# XL6019.net
KiCad netlist of a schematic drawn in Altium Designer
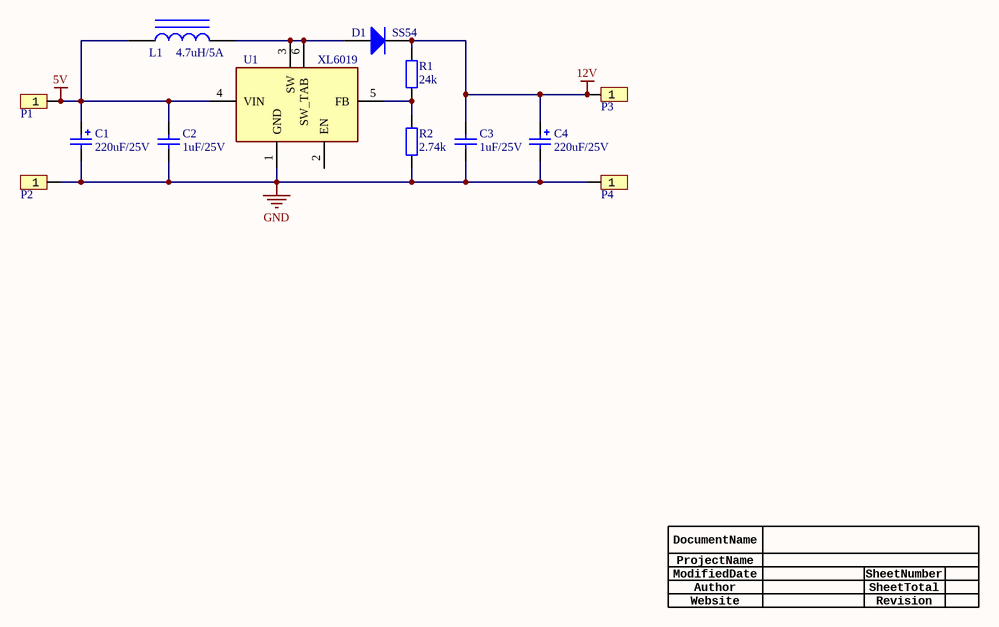
[diagram p0: XL6019.SchDoc]

(export (version "E")
  (design (tool "Eeschema 10.0.6"))
  (components
    (comp (ref "C1")
      (value "220uF/25V")
      (footprint "C_SMD-8X10")
      (description "贴片电容-有极性")
      (libsource (lib "Power_Lib_Altium") (part "CAP-POL"))
    )
    (comp (ref "C2")
      (value "1uF/25V")
      (footprint "CAP-0603")
      (description "贴片电容")
      (libsource (lib "Power_Lib_Altium") (part "CAP"))
    )
    (comp (ref "C3")
      (value "1uF/25V")
      (footprint "CAP-0603")
      (description "贴片电容")
      (libsource (lib "Power_Lib_Altium") (part "CAP"))
    )
    (comp (ref "C4")
      (value "220uF/25V")
      (footprint "C_SMD-8X10")
      (description "贴片电容-有极性")
      (libsource (lib "Power_Lib_Altium") (part "CAP-POL"))
    )
    (comp (ref "D1")
      (value "SS54")
      (footprint "DO-214AA/SMB")
      (description "二极管")
      (libsource (lib "Power_Lib_Altium") (part "DIODE"))
    )
    (comp (ref "L1")
      (value "4.7uH/5A")
      (footprint "L-0630")
      (description "电感")
      (libsource (lib "Power_Lib_Altium") (part "INDUCTOR"))
    )
    (comp (ref "P1")
      (value "HDR1x2_2.54")
      (footprint "HDR1X1_2.54")
      (description "Header")
      (libsource (lib "Power_Lib_Altium") (part "HDR1x1_2.54"))
    )
    (comp (ref "P2")
      (value "HDR1x2_2.54")
      (footprint "HDR1X1_2.54")
      (description "Header")
      (libsource (lib "Power_Lib_Altium") (part "HDR1x1_2.54"))
    )
    (comp (ref "P3")
      (value "HDR1x2_2.54")
      (footprint "HDR1X1_2.54")
      (description "Header")
      (libsource (lib "") (part "HDR1x1_2.54_1"))
    )
    (comp (ref "P4")
      (value "HDR1x2_2.54")
      (footprint "HDR1X1_2.54")
      (description "Header")
      (libsource (lib "") (part "HDR1x1_2.54_1"))
    )
    (comp (ref "R1")
      (value "24k")
      (footprint "R-0603")
      (description "贴片电阻")
      (libsource (lib "Power_Lib_Altium") (part "RES"))
    )
    (comp (ref "R2")
      (value "2.74k")
      (footprint "R-0603")
      (description "贴片电阻")
      (libsource (lib "Power_Lib_Altium") (part "RES"))
    )
    (comp (ref "U1")
      (value "XL6019")
      (footprint "TO-263-5")
      (description "DC-DC")
      (fields (field (name "MANUFACTURER_PART_NUMBER") "FT232RL") (field (name "RS PART NUMBER") "0406580P"))
      (libsource (lib "Power_Lib_Altium") (part "XL6019"))
    )
  )
  (nets
    (net (code "1") (name "5V") (class "Default")
      (node (ref "C1") (pin "1") (pinfunction "1_1") (pintype "passive"))
      (node (ref "C2") (pin "2") (pinfunction "2_2") (pintype "passive"))
      (node (ref "L1") (pin "1") (pinfunction "1_1") (pintype "passive"))
      (node (ref "P1") (pin "1") (pinfunction "1_1") (pintype "passive"))
      (node (ref "U1") (pin "4") (pinfunction "VIN_4") (pintype "power_in"))
    )
    (net (code "2") (name "12V") (class "Default")
      (node (ref "C3") (pin "2") (pinfunction "2_2") (pintype "passive"))
      (node (ref "C4") (pin "1") (pinfunction "1_1") (pintype "passive"))
      (node (ref "D1") (pin "2") (pinfunction "K_2") (pintype "passive"))
      (node (ref "P3") (pin "1") (pinfunction "1_1") (pintype "passive"))
      (node (ref "R1") (pin "2") (pinfunction "2_2") (pintype "passive"))
    )
    (net (code "3") (name "GND") (class "Default")
      (node (ref "C1") (pin "2") (pinfunction "2_2") (pintype "passive"))
      (node (ref "C2") (pin "1") (pinfunction "1_1") (pintype "passive"))
      (node (ref "C3") (pin "1") (pinfunction "1_1") (pintype "passive"))
      (node (ref "C4") (pin "2") (pinfunction "2_2") (pintype "passive"))
      (node (ref "P2") (pin "1") (pinfunction "1_1") (pintype "passive"))
      (node (ref "P4") (pin "1") (pinfunction "1_1") (pintype "passive"))
      (node (ref "R2") (pin "1") (pinfunction "1_1") (pintype "passive"))
      (node (ref "U1") (pin "1") (pinfunction "GND_1") (pintype "passive"))
    )
    (net (code "4") (name "Net-(D1-A)") (class "Default")
      (node (ref "D1") (pin "1") (pinfunction "A_1") (pintype "passive"))
      (node (ref "L1") (pin "2") (pinfunction "2_2") (pintype "passive"))
      (node (ref "U1") (pin "3") (pinfunction "SW_3") (pintype "passive"))
      (node (ref "U1") (pin "6") (pinfunction "SW_TAB_6") (pintype "passive"))
    )
    (net (code "5") (name "Net-(U1-FB)") (class "Default")
      (node (ref "R1") (pin "1") (pinfunction "1_1") (pintype "passive"))
      (node (ref "R2") (pin "2") (pinfunction "2_2") (pintype "passive"))
      (node (ref "U1") (pin "5") (pinfunction "FB_5") (pintype "power_in"))
    )
    (net (code "6") (name "unconnected-(U1-EN-Pad2)") (class "Default")
      (node (ref "U1") (pin "2") (pinfunction "EN_2") (pintype "passive"))
    )
  )
)
